# AUAV-X1_IOSOC_R1.net
KiCad netlist of a schematic drawn in Altium Designer
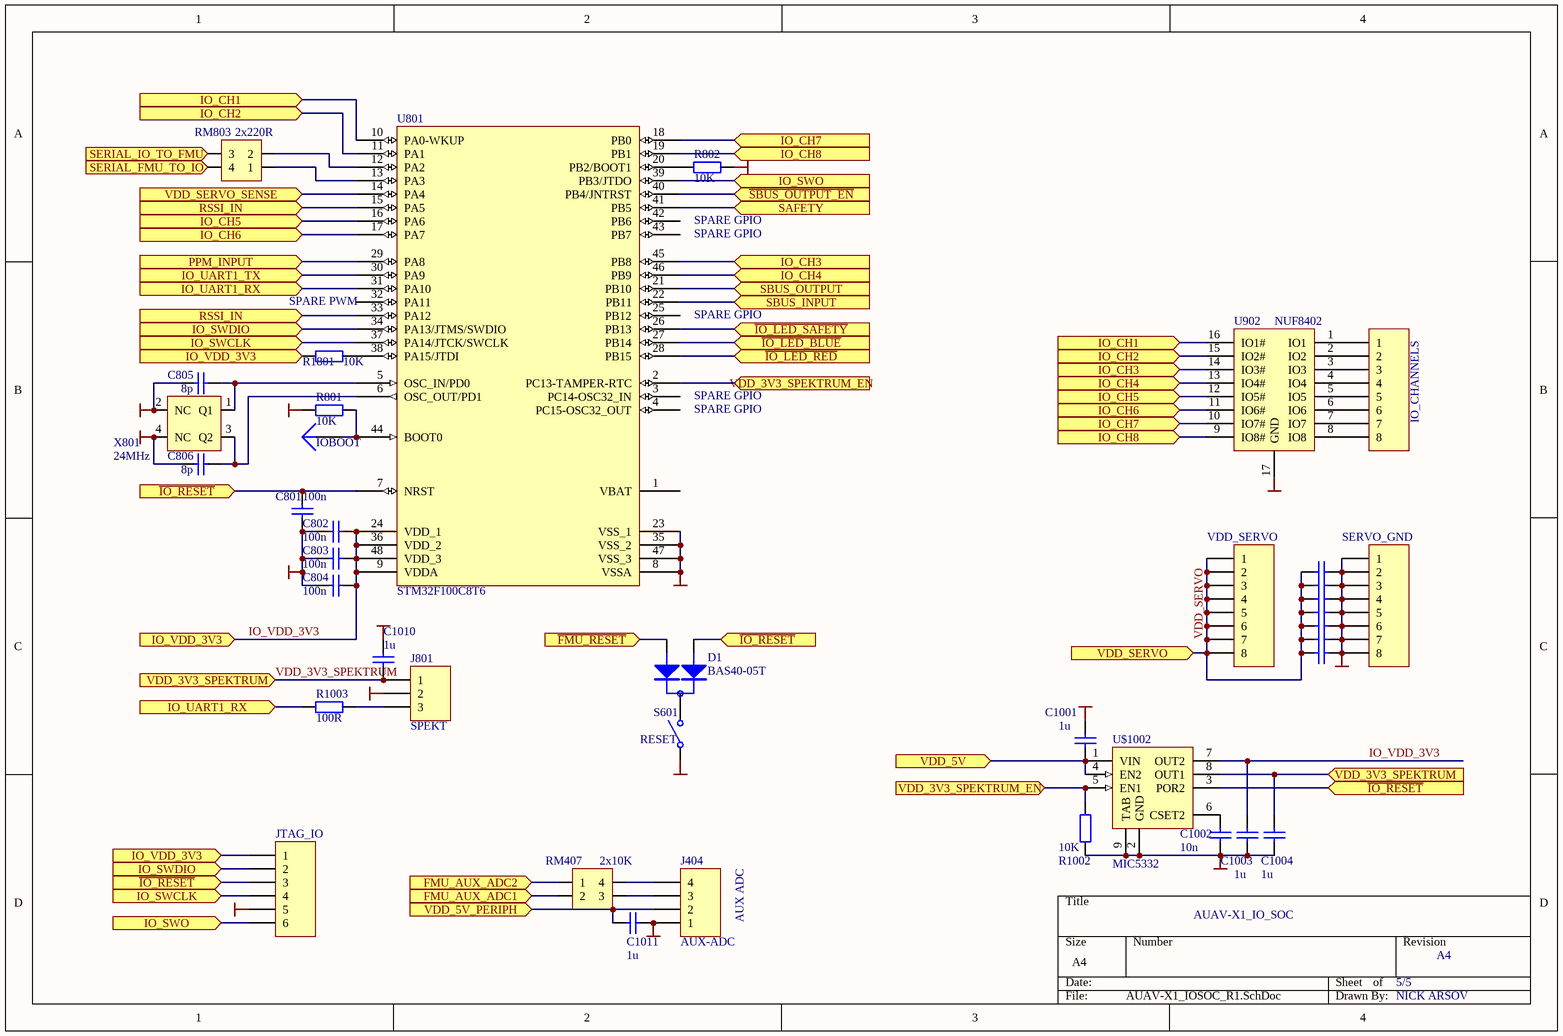
[diagram p0: AUAV-X1_IOSOC_R1.SchDoc]

(export (version "E")
  (design (tool "Eeschema 10.0.6"))
  (components
    (comp (ref "C801")
      (value "100n")
      (footprint "0402A")
      (description "Capacitor")
      (fields (field (name "PUBLISHER") "Altium Limited"))
      (libsource (lib "Miscellaneous Devices") (part "Cap"))
    )
    (comp (ref "C802")
      (value "100n")
      (footprint "0402A")
      (description "Capacitor")
      (fields (field (name "PUBLISHER") "Altium Limited"))
      (libsource (lib "Miscellaneous Devices") (part "Cap"))
    )
    (comp (ref "C803")
      (value "100n")
      (footprint "0402A")
      (description "Capacitor")
      (fields (field (name "PUBLISHER") "Altium Limited"))
      (libsource (lib "Miscellaneous Devices") (part "Cap"))
    )
    (comp (ref "C804")
      (value "100n")
      (footprint "0402A")
      (description "Capacitor")
      (fields (field (name "PUBLISHER") "Altium Limited"))
      (libsource (lib "Miscellaneous Devices") (part "Cap"))
    )
    (comp (ref "C805")
      (value "8p")
      (footprint "0402A")
      (description "Capacitor")
      (fields (field (name "PUBLISHER") "Altium Limited"))
      (libsource (lib "Miscellaneous Devices") (part "Cap"))
    )
    (comp (ref "C806")
      (value "8p")
      (footprint "0402A")
      (description "Capacitor")
      (fields (field (name "PUBLISHER") "Altium Limited"))
      (libsource (lib "Miscellaneous Devices") (part "Cap"))
    )
    (comp (ref "C1001")
      (value "1u")
      (footprint "0402A")
      (description "Capacitor")
      (fields (field (name "PUBLISHER") "Altium Limited"))
      (libsource (lib "Miscellaneous Devices") (part "Cap"))
    )
    (comp (ref "C1002")
      (value "10n")
      (footprint "0402A")
      (description "Capacitor")
      (fields (field (name "PUBLISHER") "Altium Limited"))
      (libsource (lib "Miscellaneous Devices") (part "Cap"))
    )
    (comp (ref "C1003")
      (value "1u")
      (footprint "0402A")
      (description "Capacitor")
      (fields (field (name "PUBLISHER") "Altium Limited"))
      (libsource (lib "Miscellaneous Devices") (part "Cap"))
    )
    (comp (ref "C1004")
      (value "1u")
      (footprint "0402A")
      (description "Capacitor")
      (fields (field (name "PUBLISHER") "Altium Limited"))
      (libsource (lib "Miscellaneous Devices") (part "Cap"))
    )
    (comp (ref "C1010")
      (value "1u")
      (footprint "0402A")
      (description "Capacitor")
      (fields (field (name "PUBLISHER") "Altium Limited"))
      (libsource (lib "Miscellaneous Devices") (part "Cap"))
    )
    (comp (ref "C1011")
      (value "1u")
      (footprint "0402A")
      (description "Capacitor")
      (fields (field (name "PUBLISHER") "Altium Limited"))
      (libsource (lib "Miscellaneous Devices") (part "Cap"))
    )
    (comp (ref "C3001")
      (value "100n")
      (footprint "0402A")
      (description "Capacitor")
      (fields (field (name "PUBLISHER") "Altium Limited"))
      (libsource (lib "Miscellaneous Devices") (part "Cap"))
    )
    (comp (ref "C3002")
      (value "100n")
      (footprint "0402A")
      (description "Capacitor")
      (fields (field (name "PUBLISHER") "Altium Limited"))
      (libsource (lib "Miscellaneous Devices") (part "Cap"))
    )
    (comp (ref "C3003")
      (value "100n")
      (footprint "0402A")
      (description "Capacitor")
      (fields (field (name "PUBLISHER") "Altium Limited"))
      (libsource (lib "Miscellaneous Devices") (part "Cap"))
    )
    (comp (ref "C3004")
      (value "100n")
      (footprint "0402A")
      (description "Capacitor")
      (fields (field (name "PUBLISHER") "Altium Limited"))
      (libsource (lib "Miscellaneous Devices") (part "Cap"))
    )
    (comp (ref "C3005")
      (value "100n")
      (footprint "0402A")
      (description "Capacitor")
      (fields (field (name "PUBLISHER") "Altium Limited"))
      (libsource (lib "Miscellaneous Devices") (part "Cap"))
    )
    (comp (ref "C3006")
      (value "100n")
      (footprint "0402A")
      (description "Capacitor")
      (fields (field (name "PUBLISHER") "Altium Limited"))
      (libsource (lib "Miscellaneous Devices") (part "Cap"))
    )
    (comp (ref "C3007")
      (value "100n")
      (footprint "0402A")
      (description "Capacitor")
      (fields (field (name "PUBLISHER") "Altium Limited"))
      (libsource (lib "Miscellaneous Devices") (part "Cap"))
    )
    (comp (ref "D1") (value "BAS40-05T") (footprint "SOT-523") (libsource (lib "My_Altium") (part "D-DIODE")))
    (comp (ref "IOBOOT")
      (value "Plug")
      (footprint "PAD1")
      (fields (field (name "PUBLISHER") "Altium Limited"))
      (libsource (lib "Miscellaneous Connectors") (part "Plug"))
    )
    (comp (ref "IO_CHANNELS")
      (value "Header 8")
      (footprint "HDR1X8")
      (description "Header, 8-Pin")
      (fields (field (name "PUBLISHER") "Altium Limited"))
      (libsource (lib "Miscellaneous Connectors") (part "Header 8"))
    )
    (comp (ref "J404")
      (value "AUX-ADC")
      (footprint "HDR1X4")
      (description "Header, 4-Pin")
      (fields (field (name "PUBLISHER") "Altium Limited"))
      (libsource (lib "Miscellaneous Connectors") (part "Header 4"))
    )
    (comp (ref "J801")
      (value "SPEKT")
      (footprint "hdr1x3")
      (description "Header, 3-Pin")
      (fields (field (name "PUBLISHER") "Altium Limited"))
      (libsource (lib "Miscellaneous Connectors") (part "Header 3"))
    )
    (comp (ref "JTAG_IO")
      (value "Header 6")
      (footprint "JTAG_TC2030")
      (description "Header, 6-Pin")
      (fields (field (name "PUBLISHER") "Altium Limited"))
      (libsource (lib "Miscellaneous Connectors") (part "Header 6"))
    )
    (comp (ref "R801")
      (value "10K")
      (footprint "0402A")
      (description "Resistor")
      (fields (field (name "PUBLISHER") "Altium Limited"))
      (libsource (lib "") (part "Res2_1"))
    )
    (comp (ref "R802")
      (value "10K")
      (footprint "0402A")
      (description "Resistor")
      (fields (field (name "PUBLISHER") "Altium Limited"))
      (libsource (lib "") (part "Res2_1"))
    )
    (comp (ref "R1002")
      (value "10K")
      (footprint "0402A")
      (description "Resistor")
      (fields (field (name "PUBLISHER") "Altium Limited"))
      (libsource (lib "") (part "Res2_2"))
    )
    (comp (ref "R1003")
      (value "100R")
      (footprint "0402A")
      (description "Resistor")
      (fields (field (name "PUBLISHER") "Altium Limited"))
      (libsource (lib "Miscellaneous Devices") (part "Res2"))
    )
    (comp (ref "R1801")
      (value "10K")
      (footprint "0402A")
      (description "Resistor")
      (fields (field (name "PUBLISHER") "Altium Limited"))
      (libsource (lib "") (part "Res2_1"))
    )
    (comp (ref "RM407") (value "2x10K") (footprint "RM2_0804") (libsource (lib "") (part "RES_SMD_2_1")))
    (comp (ref "RM803")
      (value "2x220R")
      (footprint "RM2_0804")
      (libsource (lib "My_Altium") (part "RES_SMD_2"))
    )
    (comp (ref "S601")
      (value "RESET")
      (footprint "OMRON_B3U_V")
      (description "Single-Pole, Single-Throw Switch")
      (fields (field (name "PUBLISHER") "Altium Limited"))
      (libsource (lib "Miscellaneous Devices") (part "SW-SPST"))
    )
    (comp (ref "SERVO_GND")
      (value "Header 8")
      (footprint "HDR1X8")
      (description "Header, 8-Pin")
      (fields (field (name "PUBLISHER") "Altium Limited"))
      (libsource (lib "Miscellaneous Connectors") (part "Header 8"))
    )
    (comp (ref "U$1002")
      (value "MIC5332")
      (footprint "MIC5332")
      (libsource (lib "My_Altium") (part "MIC5332"))
    )
    (comp (ref "U801")
      (value "STM32F100C8T6")
      (footprint "LQFP48_L")
      (description "STM32 ARM-based 32-bit MCU with 32 Kbytes Flash, 48-pin LQFP, Industrial Temperature")
      (fields (field (name "PUBLISHER") "Altium Limited"))
      (libsource (lib "ST Microcontroller 32-Bit STM32") (part "STM32F101C6T6"))
    )
    (comp (ref "U902") (value "NUF8402") (footprint "NUF8402") (libsource (lib "My_Altium") (part "NUF8402")))
    (comp (ref "VDD_SERVO")
      (value "Header 8")
      (footprint "HDR1X8")
      (description "Header, 8-Pin")
      (fields (field (name "PUBLISHER") "Altium Limited"))
      (libsource (lib "Miscellaneous Connectors") (part "Header 8"))
    )
    (comp (ref "X801")
      (value "24MHz")
      (footprint "Crystal_2.5x2")
      (libsource (lib "My_Altium") (part "Crystal_4pin"))
    )
  )
  (nets
    (net (code "1") (name "/FMU_AUX_ADC1") (class "Default")
      (node (ref "RM407") (pin "2") (pinfunction "2_2") (pintype "passive"))
    )
    (net (code "2") (name "/FMU_AUX_ADC2") (class "Default")
      (node (ref "RM407") (pin "1") (pinfunction "1_1") (pintype "passive"))
    )
    (net (code "3") (name "/IO_CH1") (class "Default")
      (node (ref "U801") (pin "10") (pinfunction "PA0-WKUP_10") (pintype "bidirectional"))
      (node (ref "U902") (pin "16") (pinfunction "IO1#_16") (pintype "passive"))
    )
    (net (code "4") (name "/IO_CH2") (class "Default")
      (node (ref "U801") (pin "11") (pinfunction "PA1_11") (pintype "bidirectional"))
      (node (ref "U902") (pin "15") (pinfunction "IO2#_15") (pintype "passive"))
    )
    (net (code "5") (name "/IO_CH3") (class "Default")
      (node (ref "U801") (pin "45") (pinfunction "PB8_45") (pintype "bidirectional"))
      (node (ref "U902") (pin "14") (pinfunction "IO3#_14") (pintype "open_collector"))
    )
    (net (code "6") (name "/IO_CH4") (class "Default")
      (node (ref "U801") (pin "46") (pinfunction "PB9_46") (pintype "bidirectional"))
      (node (ref "U902") (pin "13") (pinfunction "IO4#_13") (pintype "open_collector"))
    )
    (net (code "7") (name "/IO_CH5") (class "Default")
      (node (ref "U801") (pin "16") (pinfunction "PA6_16") (pintype "bidirectional"))
      (node (ref "U902") (pin "12") (pinfunction "IO5#_12") (pintype "open_collector"))
    )
    (net (code "8") (name "/IO_CH6") (class "Default")
      (node (ref "U801") (pin "17") (pinfunction "PA7_17") (pintype "bidirectional"))
      (node (ref "U902") (pin "11") (pinfunction "IO6#_11") (pintype "passive"))
    )
    (net (code "9") (name "/IO_CH7") (class "Default")
      (node (ref "U801") (pin "18") (pinfunction "PB0_18") (pintype "bidirectional"))
      (node (ref "U902") (pin "10") (pinfunction "IO7#_10") (pintype "passive"))
    )
    (net (code "10") (name "/IO_CH8") (class "Default")
      (node (ref "U801") (pin "19") (pinfunction "PB1_19") (pintype "bidirectional"))
      (node (ref "U902") (pin "9") (pinfunction "IO8#_9") (pintype "passive"))
    )
    (net (code "11") (name "/IO_SWCLK") (class "Default")
      (node (ref "JTAG_IO") (pin "4") (pinfunction "4_4") (pintype "passive"))
      (node (ref "U801") (pin "37") (pinfunction "PA14/JTCK/SWCLK_37") (pintype "bidirectional"))
    )
    (net (code "12") (name "/IO_SWDIO") (class "Default")
      (node (ref "JTAG_IO") (pin "2") (pinfunction "2_2") (pintype "passive"))
      (node (ref "U801") (pin "34") (pinfunction "PA13/JTMS/SWDIO_34") (pintype "bidirectional"))
    )
    (net (code "13") (name "/IO_SWO") (class "Default")
      (node (ref "JTAG_IO") (pin "6") (pinfunction "6_6") (pintype "passive"))
      (node (ref "U801") (pin "39") (pinfunction "PB3/JTDO_39") (pintype "bidirectional"))
    )
    (net (code "14") (name "/IO_UART1_RX") (class "Default")
      (node (ref "R1003") (pin "2") (pinfunction "2_2") (pintype "passive"))
      (node (ref "U801") (pin "31") (pinfunction "PA10_31") (pintype "bidirectional"))
    )
    (net (code "15") (name "/IO_UART1_TX") (class "Default")
      (node (ref "U801") (pin "30") (pinfunction "PA9_30") (pintype "bidirectional"))
    )
    (net (code "16") (name "/IO_VDD_3V3") (class "Default")
      (node (ref "C1003") (pin "2") (pinfunction "2_2") (pintype "passive"))
      (node (ref "C802") (pin "2") (pinfunction "2_2") (pintype "passive"))
      (node (ref "C803") (pin "2") (pinfunction "2_2") (pintype "passive"))
      (node (ref "C804") (pin "2") (pinfunction "2_2") (pintype "passive"))
      (node (ref "JTAG_IO") (pin "1") (pinfunction "1_1") (pintype "passive"))
      (node (ref "R1801") (pin "1") (pinfunction "1_1") (pintype "passive"))
      (node (ref "U$1002") (pin "7") (pinfunction "OUT2_7") (pintype "passive"))
      (node (ref "U801") (pin "24") (pinfunction "VDD_1_24") (pintype "power_in"))
      (node (ref "U801") (pin "36") (pinfunction "VDD_2_36") (pintype "power_in"))
      (node (ref "U801") (pin "48") (pinfunction "VDD_3_48") (pintype "power_in"))
      (node (ref "U801") (pin "9") (pinfunction "VDDA_9") (pintype "power_in"))
    )
    (net (code "17") (name "/PPM_INPUT") (class "Default")
      (node (ref "U801") (pin "29") (pinfunction "PA8_29") (pintype "bidirectional"))
    )
    (net (code "18") (name "/RSSI_IN") (class "Default")
      (node (ref "U801") (pin "15") (pinfunction "PA5_15") (pintype "bidirectional"))
      (node (ref "U801") (pin "33") (pinfunction "PA12_33") (pintype "bidirectional"))
    )
    (net (code "19") (name "/SAFETY") (class "Default")
      (node (ref "U801") (pin "41") (pinfunction "PB5_41") (pintype "bidirectional"))
    )
    (net (code "20") (name "/SBUS_INPUT") (class "Default")
      (node (ref "U801") (pin "22") (pinfunction "PB11_22") (pintype "bidirectional"))
    )
    (net (code "21") (name "/SBUS_OUTPUT") (class "Default")
      (node (ref "U801") (pin "21") (pinfunction "PB10_21") (pintype "bidirectional"))
    )
    (net (code "22") (name "/SERIAL_FMU_TO_IO") (class "Default")
      (node (ref "RM803") (pin "4") (pinfunction "4_4") (pintype "passive"))
    )
    (net (code "23") (name "/SERIAL_IO_TO_FMU") (class "Default")
      (node (ref "RM803") (pin "3") (pinfunction "3_3") (pintype "passive"))
    )
    (net (code "24") (name "/VDD_3V3_SPEKTRUM") (class "Default")
      (node (ref "C1004") (pin "2") (pinfunction "2_2") (pintype "passive"))
      (node (ref "C1010") (pin "1") (pinfunction "1_1") (pintype "passive"))
      (node (ref "J801") (pin "1") (pinfunction "1_1") (pintype "passive"))
      (node (ref "U$1002") (pin "8") (pinfunction "OUT1_8") (pintype "passive"))
    )
    (net (code "25") (name "/VDD_3V3_SPEKTRUM_EN") (class "Default")
      (node (ref "R1002") (pin "2") (pinfunction "2_2") (pintype "passive"))
      (node (ref "U$1002") (pin "5") (pinfunction "EN1_5") (pintype "input"))
      (node (ref "U801") (pin "2") (pinfunction "PC13-TAMPER-RTC_2") (pintype "bidirectional"))
    )
    (net (code "26") (name "/VDD_5V") (class "Default")
      (node (ref "C1001") (pin "1") (pinfunction "1_1") (pintype "passive"))
      (node (ref "U$1002") (pin "1") (pinfunction "VIN_1") (pintype "power_in"))
      (node (ref "U$1002") (pin "4") (pinfunction "EN2_4") (pintype "input"))
    )
    (net (code "27") (name "/VDD_5V_PERIPH") (class "Default")
      (node (ref "C1011") (pin "1") (pinfunction "1_1") (pintype "passive"))
      (node (ref "J404") (pin "2") (pinfunction "2_2") (pintype "passive"))
    )
    (net (code "28") (name "/VDD_SERVO") (class "Default")
      (node (ref "C3001") (pin "2") (pinfunction "2_2") (pintype "passive"))
      (node (ref "C3002") (pin "2") (pinfunction "2_2") (pintype "passive"))
      (node (ref "C3003") (pin "2") (pinfunction "2_2") (pintype "passive"))
      (node (ref "C3004") (pin "2") (pinfunction "2_2") (pintype "passive"))
      (node (ref "C3005") (pin "2") (pinfunction "2_2") (pintype "passive"))
      (node (ref "C3006") (pin "2") (pinfunction "2_2") (pintype "passive"))
      (node (ref "C3007") (pin "2") (pinfunction "2_2") (pintype "passive"))
      (node (ref "VDD_SERVO") (pin "1") (pinfunction "1_1") (pintype "passive"))
      (node (ref "VDD_SERVO") (pin "2") (pinfunction "2_2") (pintype "passive"))
      (node (ref "VDD_SERVO") (pin "3") (pinfunction "3_3") (pintype "passive"))
      (node (ref "VDD_SERVO") (pin "4") (pinfunction "4_4") (pintype "passive"))
      (node (ref "VDD_SERVO") (pin "5") (pinfunction "5_5") (pintype "passive"))
      (node (ref "VDD_SERVO") (pin "6") (pinfunction "6_6") (pintype "passive"))
      (node (ref "VDD_SERVO") (pin "7") (pinfunction "7_7") (pintype "passive"))
      (node (ref "VDD_SERVO") (pin "8") (pinfunction "8_8") (pintype "passive"))
    )
    (net (code "29") (name "/VDD_SERVO_SENSE") (class "Default")
      (node (ref "U801") (pin "14") (pinfunction "PA4_14") (pintype "bidirectional"))
    )
    (net (code "30") (name "/~{FMU_RESET}") (class "Default") (node (ref "D1") (pin "1") (pintype "passive")))
    (net (code "31") (name "/~{IO_LED_BLUE}") (class "Default")
      (node (ref "U801") (pin "27") (pinfunction "PB14_27") (pintype "bidirectional"))
    )
    (net (code "32") (name "/~{IO_LED_RED}") (class "Default")
      (node (ref "U801") (pin "28") (pinfunction "PB15_28") (pintype "bidirectional"))
    )
    (net (code "33") (name "/~{IO_LED_SAFETY}") (class "Default")
      (node (ref "U801") (pin "26") (pinfunction "PB13_26") (pintype "bidirectional"))
    )
    (net (code "34") (name "/~{IO_RESET}") (class "Default")
      (node (ref "C801") (pin "2") (pinfunction "2_2") (pintype "passive"))
      (node (ref "D1") (pin "2") (pintype "passive"))
      (node (ref "JTAG_IO") (pin "3") (pinfunction "3_3") (pintype "passive"))
      (node (ref "U$1002") (pin "3") (pinfunction "POR2_3") (pintype "passive"))
      (node (ref "U801") (pin "7") (pinfunction "NRST_7") (pintype "bidirectional"))
    )
    (net (code "35") (name "/~{SBUS_OUTPUT_EN}") (class "Default")
      (node (ref "U801") (pin "40") (pinfunction "PB4/JNTRST_40") (pintype "bidirectional"))
    )
    (net (code "36") (name "GND") (class "Default")
      (node (ref "C1001") (pin "2") (pinfunction "2_2") (pintype "passive"))
      (node (ref "C1002") (pin "1") (pinfunction "1_1") (pintype "passive"))
      (node (ref "C1003") (pin "1") (pinfunction "1_1") (pintype "passive"))
      (node (ref "C1004") (pin "1") (pinfunction "1_1") (pintype "passive"))
      (node (ref "C1010") (pin "2") (pinfunction "2_2") (pintype "passive"))
      (node (ref "C1011") (pin "2") (pinfunction "2_2") (pintype "passive"))
      (node (ref "C3001") (pin "1") (pinfunction "1_1") (pintype "passive"))
      (node (ref "C3002") (pin "1") (pinfunction "1_1") (pintype "passive"))
      (node (ref "C3003") (pin "1") (pinfunction "1_1") (pintype "passive"))
      (node (ref "C3004") (pin "1") (pinfunction "1_1") (pintype "passive"))
      (node (ref "C3005") (pin "1") (pinfunction "1_1") (pintype "passive"))
      (node (ref "C3006") (pin "1") (pinfunction "1_1") (pintype "passive"))
      (node (ref "C3007") (pin "1") (pinfunction "1_1") (pintype "passive"))
      (node (ref "C801") (pin "1") (pinfunction "1_1") (pintype "passive"))
      (node (ref "C802") (pin "1") (pinfunction "1_1") (pintype "passive"))
      (node (ref "C803") (pin "1") (pinfunction "1_1") (pintype "passive"))
      (node (ref "C804") (pin "1") (pinfunction "1_1") (pintype "passive"))
      (node (ref "C805") (pin "1") (pinfunction "1_1") (pintype "passive"))
      (node (ref "C806") (pin "1") (pinfunction "1_1") (pintype "passive"))
      (node (ref "J404") (pin "1") (pinfunction "1_1") (pintype "passive"))
      (node (ref "J801") (pin "2") (pinfunction "2_2") (pintype "passive"))
      (node (ref "JTAG_IO") (pin "5") (pinfunction "5_5") (pintype "passive"))
      (node (ref "R1002") (pin "1") (pinfunction "1_1") (pintype "passive"))
      (node (ref "R801") (pin "1") (pinfunction "1_1") (pintype "passive"))
      (node (ref "R802") (pin "2") (pinfunction "2_2") (pintype "passive"))
      (node (ref "S601") (pin "1") (pinfunction "COMMON_1") (pintype "passive"))
      (node (ref "SERVO_GND") (pin "1") (pinfunction "1_1") (pintype "passive"))
      (node (ref "SERVO_GND") (pin "2") (pinfunction "2_2") (pintype "passive"))
      (node (ref "SERVO_GND") (pin "3") (pinfunction "3_3") (pintype "passive"))
      (node (ref "SERVO_GND") (pin "4") (pinfunction "4_4") (pintype "passive"))
      (node (ref "SERVO_GND") (pin "5") (pinfunction "5_5") (pintype "passive"))
      (node (ref "SERVO_GND") (pin "6") (pinfunction "6_6") (pintype "passive"))
      (node (ref "SERVO_GND") (pin "7") (pinfunction "7_7") (pintype "passive"))
      (node (ref "SERVO_GND") (pin "8") (pinfunction "8_8") (pintype "passive"))
      (node (ref "U$1002") (pin "2") (pinfunction "GND_2") (pintype "power_in"))
      (node (ref "U$1002") (pin "9") (pinfunction "TAB_9") (pintype "power_in"))
      (node (ref "U801") (pin "23") (pinfunction "VSS_1_23") (pintype "power_in"))
      (node (ref "U801") (pin "35") (pinfunction "VSS_2_35") (pintype "power_in"))
      (node (ref "U801") (pin "47") (pinfunction "VSS_3_47") (pintype "power_in"))
      (node (ref "U801") (pin "8") (pinfunction "VSSA_8") (pintype "power_in"))
      (node (ref "U902") (pin "17") (pinfunction "GND_17") (pintype "passive"))
      (node (ref "X801") (pin "2") (pinfunction "NC_2") (pintype "passive"))
      (node (ref "X801") (pin "4") (pinfunction "NC_4") (pintype "passive"))
    )
    (net (code "37") (name "Net-(J404-Pad3)") (class "Default")
      (node (ref "J404") (pin "3") (pinfunction "3_3") (pintype "passive"))
      (node (ref "RM407") (pin "3") (pinfunction "3_3") (pintype "passive"))
    )
    (net (code "38") (name "Net-(J404-Pad4)") (class "Default")
      (node (ref "J404") (pin "4") (pinfunction "4_4") (pintype "passive"))
      (node (ref "RM407") (pin "4") (pinfunction "4_4") (pintype "passive"))
    )
    (net (code "39") (name "Net-(J801-Pad3)") (class "Default")
      (node (ref "J801") (pin "3") (pinfunction "3_3") (pintype "passive"))
      (node (ref "R1003") (pin "1") (pinfunction "1_1") (pintype "passive"))
    )
    (net (code "40") (name "Net-(S601-NO)") (class "Default")
      (node (ref "D1") (pin "3") (pintype "passive"))
      (node (ref "S601") (pin "2") (pinfunction "NO_2") (pintype "passive"))
    )
    (net (code "41") (name "Net-(U$1002-CSET2)") (class "Default")
      (node (ref "C1002") (pin "2") (pinfunction "2_2") (pintype "passive"))
      (node (ref "U$1002") (pin "6") (pinfunction "CSET2_6") (pintype "passive"))
    )
    (net (code "42") (name "Net-(U801-BOOT0)") (class "Default")
      (node (ref "IOBOOT") (pin "1") (pinfunction "1_1") (pintype "passive"))
      (node (ref "R801") (pin "2") (pinfunction "2_2") (pintype "passive"))
      (node (ref "U801") (pin "44") (pinfunction "BOOT0_44") (pintype "input"))
    )
    (net (code "43") (name "Net-(U801-OSC_IN{slash}PD0)") (class "Default")
      (node (ref "C805") (pin "2") (pinfunction "2_2") (pintype "passive"))
      (node (ref "U801") (pin "5") (pinfunction "OSC_IN/PD0_5") (pintype "input"))
      (node (ref "X801") (pin "1") (pinfunction "Q1_1") (pintype "passive"))
    )
    (net (code "44") (name "Net-(U801-OSC_OUT{slash}PD1)") (class "Default")
      (node (ref "C806") (pin "2") (pinfunction "2_2") (pintype "passive"))
      (node (ref "U801") (pin "6") (pinfunction "OSC_OUT/PD1_6") (pintype "output"))
      (node (ref "X801") (pin "3") (pinfunction "Q2_3") (pintype "passive"))
    )
    (net (code "45") (name "Net-(U801-PA2)") (class "Default")
      (node (ref "RM803") (pin "2") (pinfunction "2_2") (pintype "passive"))
      (node (ref "U801") (pin "12") (pinfunction "PA2_12") (pintype "bidirectional"))
    )
    (net (code "46") (name "Net-(U801-PA3)") (class "Default")
      (node (ref "RM803") (pin "1") (pinfunction "1_1") (pintype "passive"))
      (node (ref "U801") (pin "13") (pinfunction "PA3_13") (pintype "bidirectional"))
    )
    (net (code "47") (name "Net-(U801-PA15{slash}JTDI)") (class "Default")
      (node (ref "R1801") (pin "2") (pinfunction "2_2") (pintype "passive"))
      (node (ref "U801") (pin "38") (pinfunction "PA15/JTDI_38") (pintype "bidirectional"))
    )
    (net (code "48") (name "Net-(U801-PB2{slash}BOOT1)") (class "Default")
      (node (ref "R802") (pin "1") (pinfunction "1_1") (pintype "passive"))
      (node (ref "U801") (pin "20") (pinfunction "PB2/BOOT1_20") (pintype "bidirectional"))
    )
    (net (code "49") (name "Net-(U902-IO1)") (class "Default")
      (node (ref "IO_CHANNELS") (pin "1") (pinfunction "1_1") (pintype "passive"))
      (node (ref "U902") (pin "1") (pinfunction "IO1_1") (pintype "passive"))
    )
    (net (code "50") (name "Net-(U902-IO2)") (class "Default")
      (node (ref "IO_CHANNELS") (pin "2") (pinfunction "2_2") (pintype "passive"))
      (node (ref "U902") (pin "2") (pinfunction "IO2_2") (pintype "passive"))
    )
    (net (code "51") (name "Net-(U902-IO3)") (class "Default")
      (node (ref "IO_CHANNELS") (pin "3") (pinfunction "3_3") (pintype "passive"))
      (node (ref "U902") (pin "3") (pinfunction "IO3_3") (pintype "passive"))
    )
    (net (code "52") (name "Net-(U902-IO4)") (class "Default")
      (node (ref "IO_CHANNELS") (pin "4") (pinfunction "4_4") (pintype "passive"))
      (node (ref "U902") (pin "4") (pinfunction "IO4_4") (pintype "passive"))
    )
    (net (code "53") (name "Net-(U902-IO5)") (class "Default")
      (node (ref "IO_CHANNELS") (pin "5") (pinfunction "5_5") (pintype "passive"))
      (node (ref "U902") (pin "5") (pinfunction "IO5_5") (pintype "passive"))
    )
    (net (code "54") (name "Net-(U902-IO6)") (class "Default")
      (node (ref "IO_CHANNELS") (pin "6") (pinfunction "6_6") (pintype "passive"))
      (node (ref "U902") (pin "6") (pinfunction "IO6_6") (pintype "passive"))
    )
    (net (code "55") (name "Net-(U902-IO7)") (class "Default")
      (node (ref "IO_CHANNELS") (pin "7") (pinfunction "7_7") (pintype "passive"))
      (node (ref "U902") (pin "7") (pinfunction "IO7_7") (pintype "passive"))
    )
    (net (code "56") (name "Net-(U902-IO8)") (class "Default")
      (node (ref "IO_CHANNELS") (pin "8") (pinfunction "8_8") (pintype "passive"))
      (node (ref "U902") (pin "8") (pinfunction "IO8_8") (pintype "passive"))
    )
    (net (code "57") (name "unconnected-(U801-PA11-Pad32)") (class "Default")
      (node (ref "U801") (pin "32") (pinfunction "PA11_32") (pintype "bidirectional"))
    )
    (net (code "58") (name "unconnected-(U801-PB6-Pad42)") (class "Default")
      (node (ref "U801") (pin "42") (pinfunction "PB6_42") (pintype "bidirectional"))
    )
    (net (code "59") (name "unconnected-(U801-PB7-Pad43)") (class "Default")
      (node (ref "U801") (pin "43") (pinfunction "PB7_43") (pintype "bidirectional"))
    )
    (net (code "60") (name "unconnected-(U801-PB12-Pad25)") (class "Default")
      (node (ref "U801") (pin "25") (pinfunction "PB12_25") (pintype "bidirectional"))
    )
    (net (code "61") (name "unconnected-(U801-PC14-OSC32_IN-Pad3)") (class "Default")
      (node (ref "U801") (pin "3") (pinfunction "PC14-OSC32_IN_3") (pintype "bidirectional"))
    )
    (net (code "62") (name "unconnected-(U801-PC15-OSC32_OUT-Pad4)") (class "Default")
      (node (ref "U801") (pin "4") (pinfunction "PC15-OSC32_OUT_4") (pintype "bidirectional"))
    )
    (net (code "63") (name "unconnected-(U801-VBAT-Pad1)") (class "Default")
      (node (ref "U801") (pin "1") (pinfunction "VBAT_1") (pintype "power_in"))
    )
  )
)
